# openSX70-dongle_v3-6.net
KiCad netlist of a schematic drawn in EAGLE
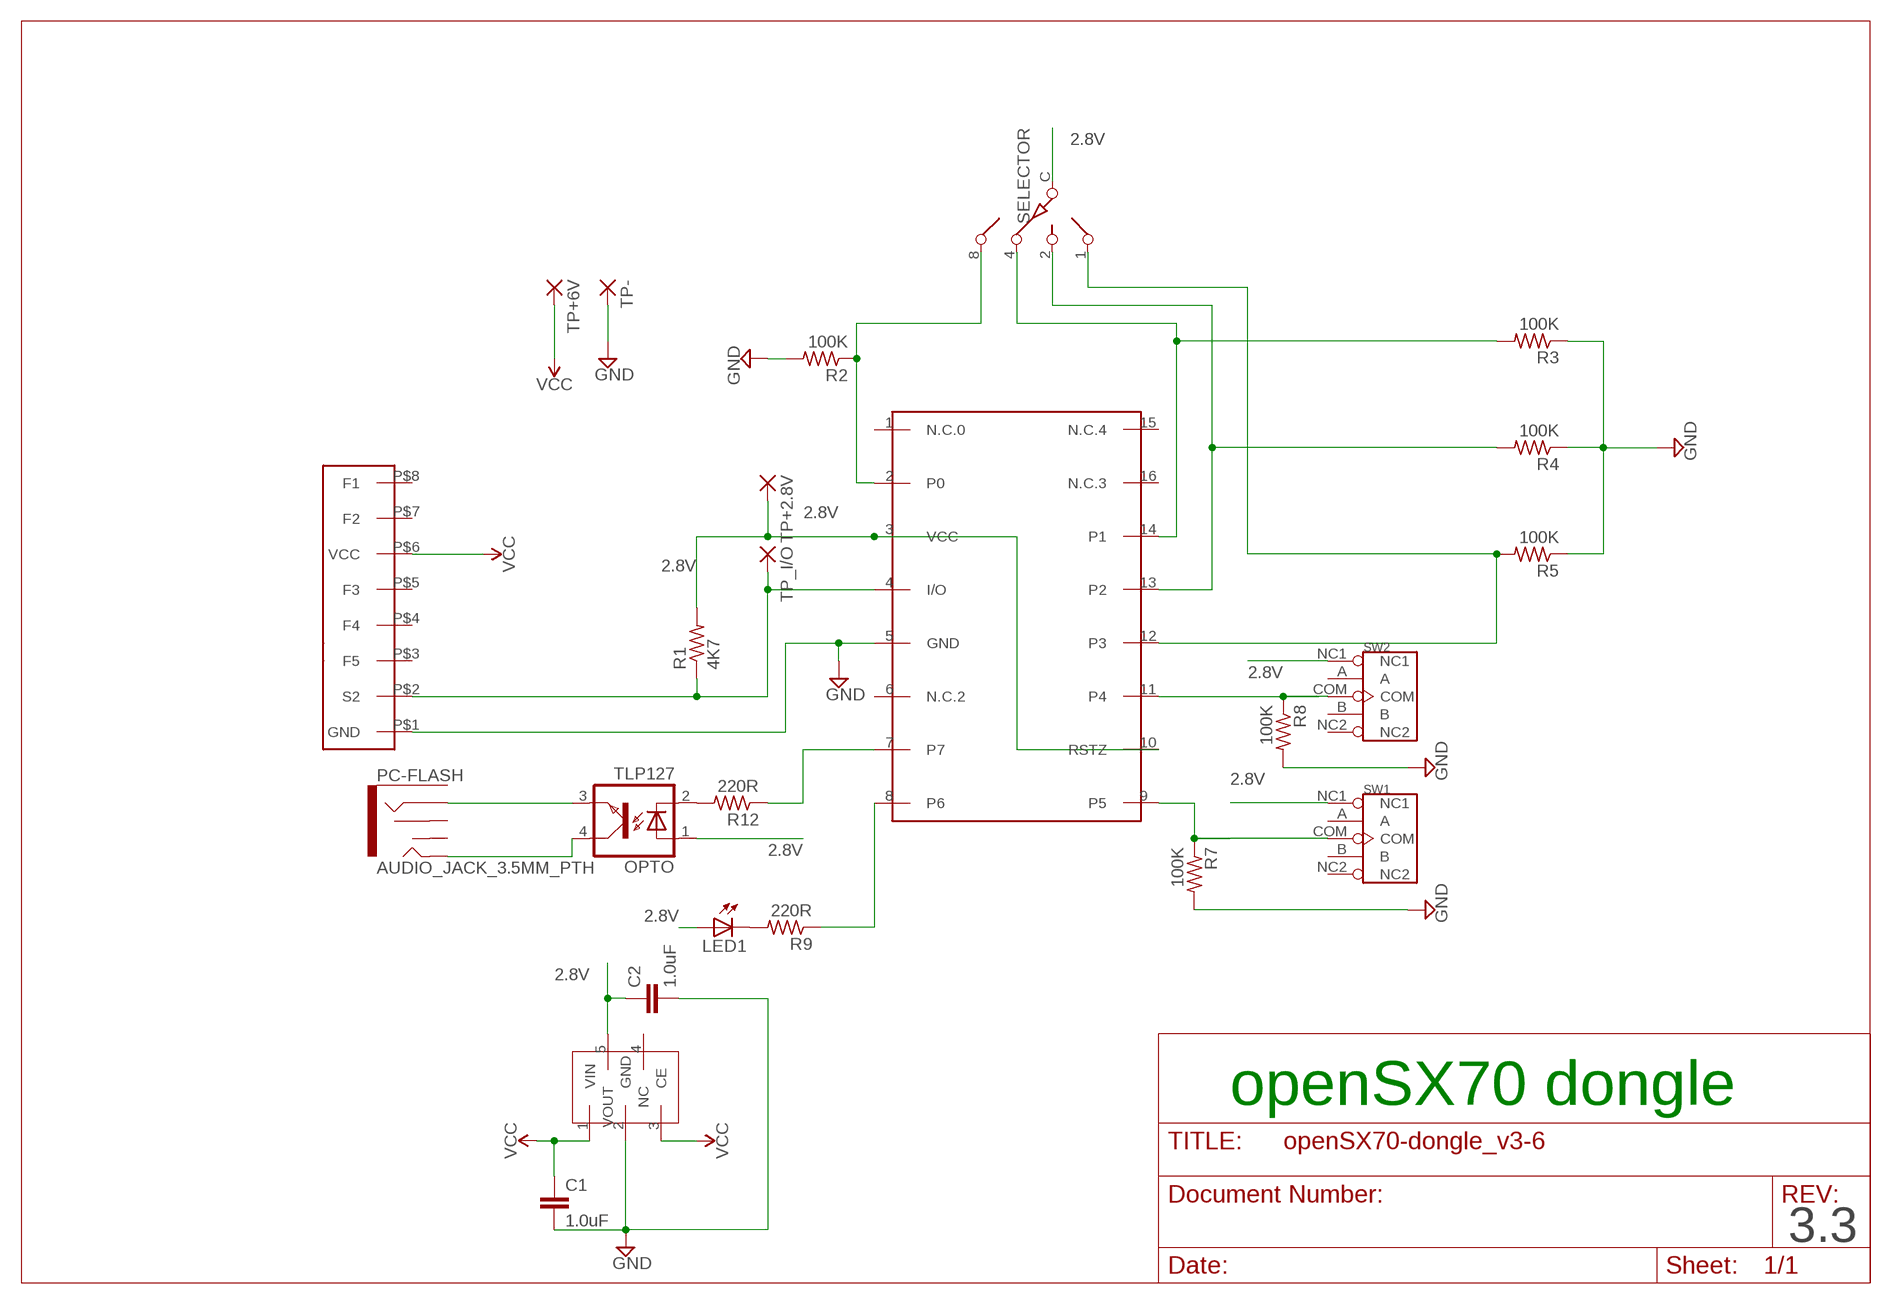
[diagram p0: schematic, sheet 1]

(export (version "E")
  (design (tool "Eeschema 10.0.6"))
  (components
    (comp (ref "C1")
      (value "1.0uF")
      (footprint "eagle-import:C0603")
      (libsource (lib "eagle-import") (part "C-EUC0603"))
    )
    (comp (ref "C2")
      (value "1.0uF")
      (footprint "eagle-import:C0603")
      (libsource (lib "eagle-import") (part "C-EUC0603"))
    )
    (comp (ref "DS2408")
      (value "DS2408")
      (footprint "eagle-import:SO16")
      (libsource (lib "eagle-import") (part "DS2408"))
    )
    (comp (ref "LED1")
      (value "LED3MM")
      (footprint "eagle-import:LED3MM")
      (libsource (lib "eagle-import") (part "LED3MM"))
    )
    (comp (ref "OPTO")
      (value "TLP127")
      (footprint "eagle-import:SO-4")
      (libsource (lib "eagle-import") (part "TLP127"))
    )
    (comp (ref "PC-FLASH")
      (value "AUDIO_JACK_3.5MM_PTH")
      (footprint "eagle-import:AUDIO-JACK")
      (libsource (lib "eagle-import") (part "AUDIO_JACK_3.5MM_PTH"))
    )
    (comp (ref "R1")
      (value "4K7")
      (footprint "eagle-import:M0805")
      (libsource (lib "eagle-import") (part "R-US_M0805"))
    )
    (comp (ref "R2")
      (value "100K")
      (footprint "eagle-import:M0805")
      (libsource (lib "eagle-import") (part "R-US_M0805"))
    )
    (comp (ref "R3")
      (value "100K")
      (footprint "eagle-import:M0805")
      (libsource (lib "eagle-import") (part "R-US_M0805"))
    )
    (comp (ref "R4")
      (value "100K")
      (footprint "eagle-import:M0805")
      (libsource (lib "eagle-import") (part "R-US_M0805"))
    )
    (comp (ref "R5")
      (value "100K")
      (footprint "eagle-import:M0805")
      (libsource (lib "eagle-import") (part "R-US_M0805"))
    )
    (comp (ref "R7")
      (value "100K")
      (footprint "eagle-import:M0805")
      (libsource (lib "eagle-import") (part "R-US_M0805"))
    )
    (comp (ref "R8")
      (value "100K")
      (footprint "eagle-import:M0805")
      (libsource (lib "eagle-import") (part "R-US_M0805"))
    )
    (comp (ref "R9")
      (value "220R")
      (footprint "eagle-import:M0805")
      (libsource (lib "eagle-import") (part "R-US_M0805"))
    )
    (comp (ref "R12")
      (value "220R")
      (footprint "eagle-import:M0805")
      (libsource (lib "eagle-import") (part "R-US_M0805"))
    )
    (comp (ref "REG")
      (value "NCP4688")
      (footprint "eagle-import:SOT-23-5")
      (libsource (lib "eagle-import") (part "NCP4688"))
    )
    (comp (ref "SELECTOR")
      (value "SW-C16")
      (footprint "eagle-import:SW-C16")
      (libsource (lib "eagle-import") (part "SW-C16"))
    )
    (comp (ref "SW1")
      (value "DIP-TOGGLE-SWITCH-ON-ON(3+2P-8.8X4.6MM)-90D")
      (footprint "eagle-import:SW5-2.0-8.8X4.4X4.7MM-90D")
      (fields (field (name "MPN") "3P-2.0-90D3P-2.0-90D-REINFORCE"))
      (libsource (lib "eagle-import") (part "DIP-TOGGLE-SWITCH-ON-ON(3+2P-8.8X4.6MM)-90D"))
    )
    (comp (ref "SW2")
      (value "DIP-TOGGLE-SWITCH-ON-ON(3+2P-8.8X4.6MM)-90D")
      (footprint "eagle-import:SW5-2.0-8.8X4.4X4.7MM-90D")
      (fields (field (name "MPN") "3P-2.0-90D3P-2.0-90D-REINFORCE"))
      (libsource (lib "eagle-import") (part "DIP-TOGGLE-SWITCH-ON-ON(3+2P-8.8X4.6MM)-90D"))
    )
    (comp (ref "TP+2.8V")
      (value "SMD2")
      (footprint "eagle-import:SMD1,27-2,54")
      (libsource (lib "eagle-import") (part "SMD2"))
    )
    (comp (ref "TP+6V")
      (value "SMD2")
      (footprint "eagle-import:SMD1,27-2,54")
      (libsource (lib "eagle-import") (part "SMD2"))
    )
    (comp (ref "TP-")
      (value "SMD2")
      (footprint "eagle-import:SMD1,27-2,54")
      (libsource (lib "eagle-import") (part "SMD2"))
    )
    (comp (ref "TP_I/O")
      (value "SMD2")
      (footprint "eagle-import:SMD1,27-2,54")
      (libsource (lib "eagle-import") (part "SMD2"))
    )
    (comp (ref "U$1")
      (value "FLASH-EDGE-CONNECTOR")
      (footprint "eagle-import:FLASH-EDGE-8")
      (libsource (lib "eagle-import") (part "FLASH-EDGE-CONNECTOR"))
    )
  )
  (nets
    (net (code "1") (name "/2.8V") (class "Default")
      (node (ref "C2") (pin "1") (pinfunction "1_1") (pintype "passive"))
      (node (ref "DS2408") (pin "10") (pinfunction "RSTZ_10") (pintype "bidirectional"))
      (node (ref "DS2408") (pin "3") (pinfunction "VCC_3") (pintype "bidirectional"))
      (node (ref "LED1") (pin "A") (pinfunction "A_A") (pintype "passive"))
      (node (ref "OPTO") (pin "1") (pinfunction "A_1") (pintype "passive"))
      (node (ref "R1") (pin "2") (pinfunction "2_2") (pintype "passive"))
      (node (ref "REG") (pin "5") (pinfunction "VOUT_5") (pintype "bidirectional"))
      (node (ref "SELECTOR") (pin "C") (pinfunction "C_C") (pintype "passive"))
      (node (ref "SW1") (pin "NC1") (pinfunction "NC1_NC1") (pintype "bidirectional"))
      (node (ref "SW2") (pin "NC1") (pinfunction "NC1_NC1") (pintype "bidirectional"))
      (node (ref "TP+2.8V") (pin "1") (pinfunction "P_1") (pintype "passive"))
    )
    (net (code "2") (name "GND") (class "Default")
      (node (ref "C1") (pin "2") (pinfunction "2_2") (pintype "passive"))
      (node (ref "C2") (pin "2") (pinfunction "2_2") (pintype "passive"))
      (node (ref "DS2408") (pin "5") (pinfunction "GND_5") (pintype "bidirectional"))
      (node (ref "R2") (pin "2") (pinfunction "2_2") (pintype "passive"))
      (node (ref "R3") (pin "1") (pinfunction "1_1") (pintype "passive"))
      (node (ref "R4") (pin "1") (pinfunction "1_1") (pintype "passive"))
      (node (ref "R5") (pin "1") (pinfunction "1_1") (pintype "passive"))
      (node (ref "R7") (pin "2") (pinfunction "2_2") (pintype "passive"))
      (node (ref "R8") (pin "2") (pinfunction "2_2") (pintype "passive"))
      (node (ref "REG") (pin "2") (pinfunction "GND_2") (pintype "bidirectional"))
      (node (ref "TP-") (pin "1") (pinfunction "P_1") (pintype "passive"))
      (node (ref "U$1") (pin "P$1") (pinfunction "GND_P$1") (pintype "bidirectional"))
    )
    (net (code "3") (name "Net-(DS2408-I{slash}O)") (class "Default")
      (node (ref "DS2408") (pin "4") (pinfunction "I/O_4") (pintype "bidirectional"))
      (node (ref "R1") (pin "1") (pinfunction "1_1") (pintype "passive"))
      (node (ref "TP_I/O") (pin "1") (pinfunction "P_1") (pintype "passive"))
      (node (ref "U$1") (pin "P$2") (pinfunction "S2_P$2") (pintype "bidirectional"))
    )
    (net (code "4") (name "Net-(DS2408-P0)") (class "Default")
      (node (ref "DS2408") (pin "2") (pinfunction "P0_2") (pintype "bidirectional"))
      (node (ref "R2") (pin "1") (pinfunction "1_1") (pintype "passive"))
      (node (ref "SELECTOR") (pin "8") (pinfunction "8_8") (pintype "passive"))
    )
    (net (code "5") (name "Net-(DS2408-P1)") (class "Default")
      (node (ref "DS2408") (pin "14") (pinfunction "P1_14") (pintype "bidirectional"))
      (node (ref "R3") (pin "2") (pinfunction "2_2") (pintype "passive"))
      (node (ref "SELECTOR") (pin "4") (pinfunction "4_4") (pintype "passive"))
    )
    (net (code "6") (name "Net-(DS2408-P2)") (class "Default")
      (node (ref "DS2408") (pin "13") (pinfunction "P2_13") (pintype "bidirectional"))
      (node (ref "R4") (pin "2") (pinfunction "2_2") (pintype "passive"))
      (node (ref "SELECTOR") (pin "2") (pinfunction "2_2") (pintype "passive"))
    )
    (net (code "7") (name "Net-(DS2408-P3)") (class "Default")
      (node (ref "DS2408") (pin "12") (pinfunction "P3_12") (pintype "bidirectional"))
      (node (ref "R5") (pin "2") (pinfunction "2_2") (pintype "passive"))
      (node (ref "SELECTOR") (pin "1") (pinfunction "1_1") (pintype "passive"))
    )
    (net (code "8") (name "Net-(DS2408-P4)") (class "Default")
      (node (ref "DS2408") (pin "11") (pinfunction "P4_11") (pintype "bidirectional"))
      (node (ref "R8") (pin "1") (pinfunction "1_1") (pintype "passive"))
      (node (ref "SW2") (pin "COM") (pinfunction "COM_COM") (pintype "bidirectional"))
    )
    (net (code "9") (name "Net-(DS2408-P5)") (class "Default")
      (node (ref "DS2408") (pin "9") (pinfunction "P5_9") (pintype "bidirectional"))
      (node (ref "R7") (pin "1") (pinfunction "1_1") (pintype "passive"))
      (node (ref "SW1") (pin "COM") (pinfunction "COM_COM") (pintype "bidirectional"))
    )
    (net (code "10") (name "Net-(DS2408-P6)") (class "Default")
      (node (ref "DS2408") (pin "8") (pinfunction "P6_8") (pintype "bidirectional"))
      (node (ref "R9") (pin "1") (pinfunction "1_1") (pintype "passive"))
    )
    (net (code "11") (name "Net-(DS2408-P7)") (class "Default")
      (node (ref "DS2408") (pin "7") (pinfunction "P7_7") (pintype "bidirectional"))
      (node (ref "R12") (pin "1") (pinfunction "1_1") (pintype "passive"))
    )
    (net (code "12") (name "Net-(LED1-C)") (class "Default")
      (node (ref "LED1") (pin "K") (pinfunction "C_K") (pintype "passive"))
      (node (ref "R9") (pin "2") (pinfunction "2_2") (pintype "passive"))
    )
    (net (code "13") (name "Net-(OPTO-C)") (class "Default")
      (node (ref "OPTO") (pin "2") (pinfunction "C_2") (pintype "passive"))
      (node (ref "R12") (pin "2") (pinfunction "2_2") (pintype "passive"))
    )
    (net (code "14") (name "Net-(OPTO-COL)") (class "Default")
      (node (ref "OPTO") (pin "4") (pinfunction "COL_4") (pintype "passive"))
      (node (ref "PC-FLASH") (pin "TIP") (pinfunction "TIP_TIP") (pintype "bidirectional"))
    )
    (net (code "15") (name "Net-(OPTO-EMIT)") (class "Default")
      (node (ref "OPTO") (pin "3") (pinfunction "EMIT_3") (pintype "passive"))
      (node (ref "PC-FLASH") (pin "RING") (pinfunction "RING_RING") (pintype "bidirectional"))
    )
    (net (code "16") (name "VCC") (class "Default")
      (node (ref "C1") (pin "1") (pinfunction "1_1") (pintype "passive"))
      (node (ref "REG") (pin "1") (pinfunction "VIN_1") (pintype "bidirectional"))
      (node (ref "REG") (pin "3") (pinfunction "CE_3") (pintype "bidirectional"))
      (node (ref "TP+6V") (pin "1") (pinfunction "P_1") (pintype "passive"))
      (node (ref "U$1") (pin "P$6") (pinfunction "VCC_P$6") (pintype "bidirectional"))
    )
    (net (code "17") (name "unconnected-(DS2408-N.C.0-Pad1)") (class "Default")
      (node (ref "DS2408") (pin "1") (pinfunction "N.C.0_1") (pintype "bidirectional"))
    )
    (net (code "18") (name "unconnected-(DS2408-N.C.2-Pad6)") (class "Default")
      (node (ref "DS2408") (pin "6") (pinfunction "N.C.2_6") (pintype "bidirectional"))
    )
    (net (code "19") (name "unconnected-(DS2408-N.C.3-Pad16)") (class "Default")
      (node (ref "DS2408") (pin "16") (pinfunction "N.C.3_16") (pintype "bidirectional"))
    )
    (net (code "20") (name "unconnected-(DS2408-N.C.4-Pad15)") (class "Default")
      (node (ref "DS2408") (pin "15") (pinfunction "N.C.4_15") (pintype "bidirectional"))
    )
    (net (code "21") (name "unconnected-(PC-FLASH-PadRSH)") (class "Default")
      (node (ref "PC-FLASH") (pin "RSH") (pinfunction "RSH_RSH") (pintype "bidirectional"))
    )
    (net (code "22") (name "unconnected-(PC-FLASH-PadSLEEVE)") (class "Default")
      (node (ref "PC-FLASH") (pin "SLEEVE") (pinfunction "SLEEVE_SLEEVE") (pintype "bidirectional"))
    )
    (net (code "23") (name "unconnected-(PC-FLASH-PadTSH)") (class "Default")
      (node (ref "PC-FLASH") (pin "TSH") (pinfunction "TSH_TSH") (pintype "bidirectional"))
    )
    (net (code "24") (name "unconnected-(REG-NC-Pad4)") (class "Default")
      (node (ref "REG") (pin "4") (pinfunction "NC_4") (pintype "bidirectional"))
    )
    (net (code "25") (name "unconnected-(SW1-PadA)") (class "Default")
      (node (ref "SW1") (pin "A") (pinfunction "A_A") (pintype "bidirectional"))
    )
    (net (code "26") (name "unconnected-(SW1-PadB)") (class "Default")
      (node (ref "SW1") (pin "B") (pinfunction "B_B") (pintype "bidirectional"))
    )
    (net (code "27") (name "unconnected-(SW1-PadNC2)") (class "Default")
      (node (ref "SW1") (pin "NC2") (pinfunction "NC2_NC2") (pintype "bidirectional"))
    )
    (net (code "28") (name "unconnected-(SW2-PadA)") (class "Default")
      (node (ref "SW2") (pin "A") (pinfunction "A_A") (pintype "bidirectional"))
    )
    (net (code "29") (name "unconnected-(SW2-PadB)") (class "Default")
      (node (ref "SW2") (pin "B") (pinfunction "B_B") (pintype "bidirectional"))
    )
    (net (code "30") (name "unconnected-(SW2-PadNC2)") (class "Default")
      (node (ref "SW2") (pin "NC2") (pinfunction "NC2_NC2") (pintype "bidirectional"))
    )
    (net (code "31") (name "unconnected-(U$1-F1-PadP$8)") (class "Default")
      (node (ref "U$1") (pin "P$8") (pinfunction "F1_P$8") (pintype "bidirectional"))
    )
    (net (code "32") (name "unconnected-(U$1-F2-PadP$7)") (class "Default")
      (node (ref "U$1") (pin "P$7") (pinfunction "F2_P$7") (pintype "bidirectional"))
    )
    (net (code "33") (name "unconnected-(U$1-F3-PadP$5)") (class "Default")
      (node (ref "U$1") (pin "P$5") (pinfunction "F3_P$5") (pintype "bidirectional"))
    )
    (net (code "34") (name "unconnected-(U$1-F4-PadP$4)") (class "Default")
      (node (ref "U$1") (pin "P$4") (pinfunction "F4_P$4") (pintype "bidirectional"))
    )
    (net (code "35") (name "unconnected-(U$1-F5-PadP$3)") (class "Default")
      (node (ref "U$1") (pin "P$3") (pinfunction "F5_P$3") (pintype "bidirectional"))
    )
  )
)
